# MCU.net
KiCad netlist of a schematic drawn in Altium Designer
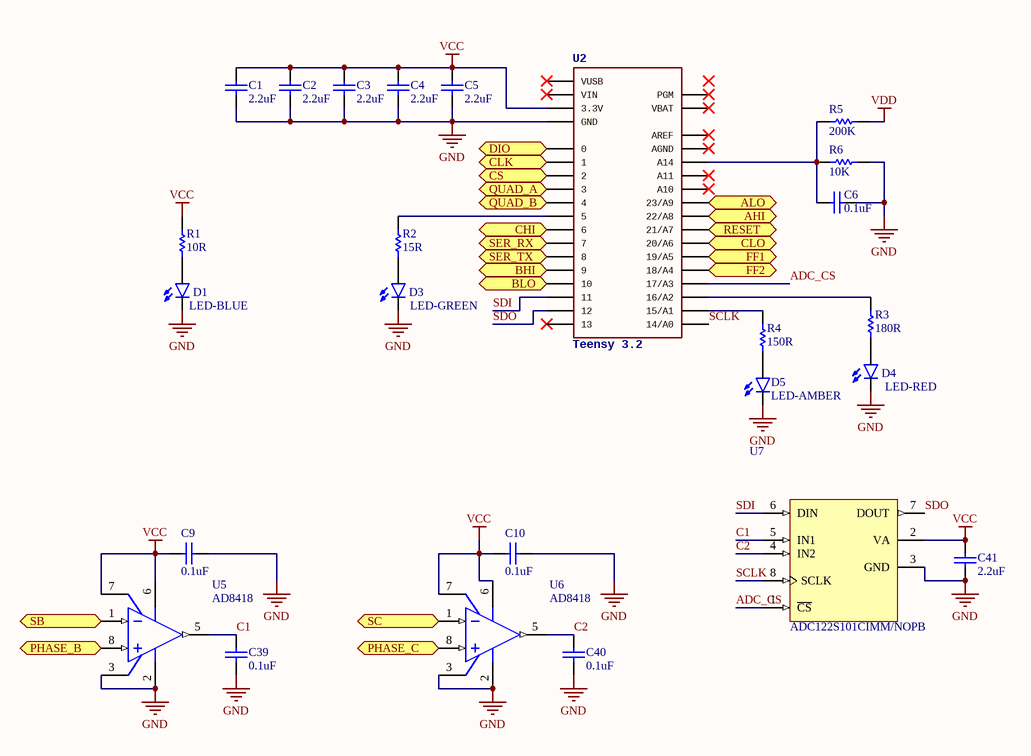
[diagram p0: MCU.SchDoc]

(export (version "E")
  (design (tool "Eeschema 10.0.6"))
  (components
    (comp (ref "C1")
      (value "2.2uF")
      (footprint "CAPC0603(1608)55_N")
      (description "CAP 2.2uF 16V Â±10% 0603 (1608 Metric) Thickness 0.55mm SMD")
      (fields (field (name "TOLERANCE") "Â±10%"))
      (libsource (lib "Altium Content Vault") (part "CMP-1035-02762-1"))
    )
    (comp (ref "C2")
      (value "2.2uF")
      (footprint "CAPC0603(1608)55_N")
      (description "CAP 2.2uF 16V Â±10% 0603 (1608 Metric) Thickness 0.55mm SMD")
      (fields (field (name "TOLERANCE") "Â±10%"))
      (libsource (lib "Altium Content Vault") (part "CMP-1035-02762-1"))
    )
    (comp (ref "C3")
      (value "2.2uF")
      (footprint "CAPC0603(1608)55_N")
      (description "CAP 2.2uF 16V Â±10% 0603 (1608 Metric) Thickness 0.55mm SMD")
      (fields (field (name "TOLERANCE") "Â±10%"))
      (libsource (lib "Altium Content Vault") (part "CMP-1035-02762-1"))
    )
    (comp (ref "C4")
      (value "2.2uF")
      (footprint "CAPC0603(1608)55_N")
      (description "CAP 2.2uF 16V Â±10% 0603 (1608 Metric) Thickness 0.55mm SMD")
      (fields (field (name "TOLERANCE") "Â±10%"))
      (libsource (lib "Altium Content Vault") (part "CMP-1035-02762-1"))
    )
    (comp (ref "C5")
      (value "2.2uF")
      (footprint "CAPC0603(1608)55_N")
      (description "CAP 2.2uF 16V Â±10% 0603 (1608 Metric) Thickness 0.55mm SMD")
      (fields (field (name "TOLERANCE") "Â±10%"))
      (libsource (lib "Altium Content Vault") (part "CMP-1035-02762-1"))
    )
    (comp (ref "C6")
      (value "0.1uF")
      (footprint "CAPC0603(1608)100_L")
      (description "CAP 100nF 50V Â±5% 0603 (1608 Metric) Thickness 1mm SMD")
      (fields (field (name "TOLERANCE") "Â±5%"))
      (libsource (lib "Altium Content Vault") (part "CMP-1035-02591-1"))
    )
    (comp (ref "C9")
      (value "0.1uF")
      (footprint "CAPC0603(1608)100_L")
      (description "CAP 100nF 6.3V Â±20% 0603 (1608 Metric) Thickness 1mm SMD")
      (fields (field (name "TOLERANCE") "Â±20%"))
      (libsource (lib "Altium Content Vault") (part "CMP-1035-02577-1"))
    )
    (comp (ref "C10")
      (value "0.1uF")
      (footprint "CAPC0603(1608)100_L")
      (description "CAP 100nF 6.3V Â±20% 0603 (1608 Metric) Thickness 1mm SMD")
      (fields (field (name "TOLERANCE") "Â±20%"))
      (libsource (lib "Altium Content Vault") (part "CMP-1035-02577-1"))
    )
    (comp (ref "C39")
      (value "0.1uF")
      (footprint "CAPC0603(1608)100_N")
      (description "CAP 100nF 6.3V ±5% 0603 (1608 Metric) Thickness 1mm SMD")
      (fields (field (name "TOLERANCE") "Â±5%"))
      (libsource (lib "Altium Content Vault") (part "CAP"))
    )
    (comp (ref "C40")
      (value "0.1uF")
      (footprint "CAPC0603(1608)100_N")
      (description "CAP 100nF 6.3V ±5% 0603 (1608 Metric) Thickness 1mm SMD")
      (fields (field (name "TOLERANCE") "Â±5%"))
      (libsource (lib "Altium Content Vault") (part "CAP"))
    )
    (comp (ref "C41")
      (value "2.2uF")
      (footprint "CAPC0603(1608)100_M")
      (description "CAP 2.2uF 6.3V ±10% 0603 (1608 Metric) Thickness 1mm SMD")
      (fields (field (name "TOLERANCE") "Â±10%"))
      (libsource (lib "Altium Content Vault") (part "CAP"))
    )
    (comp (ref "D1")
      (value "LED-BLUE")
      (footprint "LED-1206")
      (libsource (lib "Components") (part "LED-BLUE1206"))
    )
    (comp (ref "D3")
      (value "LED-GREEN")
      (footprint "LED-1206")
      (libsource (lib "Components") (part "LED-GREEN1206"))
    )
    (comp (ref "D4")
      (value "LED-RED")
      (footprint "LED-1206")
      (libsource (lib "Components") (part "LED-RED1206"))
    )
    (comp (ref "D5")
      (value "LED-AMBER")
      (footprint "LED-1206")
      (libsource (lib "Components") (part "LED-AMBER1206"))
    )
    (comp (ref "R1")
      (value "10R")
      (footprint "RESC0603(1608)_N")
      (description "10R 0.1W 5% 0603 (1608 Metric)  SMD")
      (fields (field (name "TOLERANCE") "5 %") (field (name "POWER") "0.1 W"))
      (libsource (lib "Altium Content Vault") (part "CMP-1012-00026-1"))
    )
    (comp (ref "R2")
      (value "15R")
      (footprint "RESC0603(1608)_N")
      (description "15R 0.1W 5% 0603 (1608 Metric)  SMD")
      (fields (field (name "TOLERANCE") "5 %") (field (name "POWER") "0.1 W"))
      (libsource (lib "Altium Content Vault") (part "CMP-1012-00030-1"))
    )
    (comp (ref "R3")
      (value "180R")
      (footprint "RESC0603(1608)_N")
      (description "180R 0.1W 5% 0603 (1608 Metric)  SMD")
      (fields (field (name "POWER") "0.1 W") (field (name "TOLERANCE") "5 %"))
      (libsource (lib "Altium Content Vault") (part "CMP-1012-00056-1"))
    )
    (comp (ref "R4")
      (value "150R")
      (footprint "RESC0603(1608)_N")
      (description "150R 0.1W 5% 0603 (1608 Metric)  SMD")
      (fields (field (name "POWER") "0.1 W") (field (name "TOLERANCE") "5 %"))
      (libsource (lib "Altium Content Vault") (part "CMP-1012-00054-1"))
    )
    (comp (ref "R5")
      (value "200K")
      (footprint "RESC0603(1608)_N")
      (description "200K 0.1W 5% 0603 (1608 Metric)  SMD")
      (fields (field (name "POWER") "0.1 W") (field (name "TOLERANCE") "5 %"))
      (libsource (lib "Altium Content Vault") (part "CMP-1012-00129-1"))
    )
    (comp (ref "R6")
      (value "10K")
      (footprint "RESC0603(1608)_N")
      (description "10K 0.1W 5% 0603 (1608 Metric)  SMD")
      (fields (field (name "TOLERANCE") "5 %") (field (name "POWER") "0.1 W"))
      (libsource (lib "Altium Content Vault") (part "RES"))
    )
    (comp (ref "U2")
      (value "Teensy 3.2")
      (footprint "TEENSY_3.0+4")
      (libsource (lib "Teensy3") (part "TEENSY_3.0+4"))
    )
    (comp (ref "U5") (value "AD8418") (footprint "MSOP-8") (libsource (lib "Components") (part "AD8418")))
    (comp (ref "U6") (value "AD8418") (footprint "MSOP-8") (libsource (lib "Components") (part "AD8418")))
    (comp (ref "U7")
      (value "ADC122S101CIMM/NOPB")
      (footprint "MUA08A_N")
      (description "2 Channel, 500 kSPS to 1 MSPS 12-Bit A/D Converter, 8-pin Mini SOIC, Pb-Free")
      (fields (field (name "MANUFACTURER") "National Semiconductor"))
      (libsource (lib "Altium Content Vault") (part "CON-ADC-ADC102S101CIMM"))
    )
  )
  (nets
    (net (code "1") (name "/ADC_CS") (class "Default")
      (node (ref "U2") (pin "17/A3") (pinfunction "17/A3_17/A3") (pintype "passive"))
      (node (ref "U7") (pin "1") (pinfunction "~{CS}_1") (pintype "input"))
    )
    (net (code "2") (name "/AHI") (class "Default")
      (node (ref "U2") (pin "22/A8") (pinfunction "22/A8_22/A8") (pintype "passive"))
    )
    (net (code "3") (name "/ALO") (class "Default")
      (node (ref "U2") (pin "23/A9") (pinfunction "23/A9_23/A9") (pintype "passive"))
    )
    (net (code "4") (name "/BHI") (class "Default")
      (node (ref "U2") (pin "9") (pinfunction "9_9") (pintype "passive"))
    )
    (net (code "5") (name "/BLO") (class "Default")
      (node (ref "U2") (pin "10") (pinfunction "10_10") (pintype "passive"))
    )
    (net (code "6") (name "/C1") (class "Default")
      (node (ref "C39") (pin "2") (pinfunction "2_2") (pintype "passive"))
      (node (ref "U5") (pin "5") (pinfunction "OUT_5") (pintype "output"))
      (node (ref "U7") (pin "5") (pinfunction "IN1_5") (pintype "input"))
    )
    (net (code "7") (name "/C2") (class "Default")
      (node (ref "C40") (pin "2") (pinfunction "2_2") (pintype "passive"))
      (node (ref "U6") (pin "5") (pinfunction "OUT_5") (pintype "output"))
      (node (ref "U7") (pin "4") (pinfunction "IN2_4") (pintype "input"))
    )
    (net (code "8") (name "/CHI") (class "Default")
      (node (ref "U2") (pin "6") (pinfunction "6_6") (pintype "passive"))
    )
    (net (code "9") (name "/CLK") (class "Default")
      (node (ref "U2") (pin "1") (pinfunction "1_1") (pintype "passive"))
    )
    (net (code "10") (name "/CLO") (class "Default")
      (node (ref "U2") (pin "20/A6") (pinfunction "20/A6_20/A6") (pintype "passive"))
    )
    (net (code "11") (name "/CS") (class "Default")
      (node (ref "U2") (pin "2") (pinfunction "2_2") (pintype "passive"))
    )
    (net (code "12") (name "/DIO") (class "Default")
      (node (ref "U2") (pin "0") (pinfunction "0_0") (pintype "passive"))
    )
    (net (code "13") (name "/FF1") (class "Default")
      (node (ref "U2") (pin "19/A5") (pinfunction "19/A5_19/A5") (pintype "passive"))
    )
    (net (code "14") (name "/FF2") (class "Default")
      (node (ref "U2") (pin "18/A4") (pinfunction "18/A4_18/A4") (pintype "passive"))
    )
    (net (code "15") (name "/PHASE_B") (class "Default")
      (node (ref "U5") (pin "8") (pinfunction "IN+_8") (pintype "input"))
    )
    (net (code "16") (name "/PHASE_C") (class "Default")
      (node (ref "U6") (pin "8") (pinfunction "IN+_8") (pintype "input"))
    )
    (net (code "17") (name "/QUAD_A") (class "Default")
      (node (ref "U2") (pin "3") (pinfunction "3_3") (pintype "passive"))
    )
    (net (code "18") (name "/QUAD_B") (class "Default")
      (node (ref "U2") (pin "4") (pinfunction "4_4") (pintype "passive"))
    )
    (net (code "19") (name "/RESET") (class "Default")
      (node (ref "U2") (pin "21/A7") (pinfunction "21/A7_21/A7") (pintype "passive"))
    )
    (net (code "20") (name "/SB") (class "Default")
      (node (ref "U5") (pin "1") (pinfunction "IN-_1") (pintype "input"))
    )
    (net (code "21") (name "/SC") (class "Default")
      (node (ref "U6") (pin "1") (pinfunction "IN-_1") (pintype "input"))
    )
    (net (code "22") (name "/SCLK") (class "Default")
      (node (ref "U2") (pin "14/A0") (pinfunction "14/A0_14/A0") (pintype "passive"))
      (node (ref "U7") (pin "8") (pinfunction "SCLK_8") (pintype "input"))
    )
    (net (code "23") (name "/SDI") (class "Default")
      (node (ref "U2") (pin "11") (pinfunction "11_11") (pintype "passive"))
      (node (ref "U7") (pin "6") (pinfunction "DIN_6") (pintype "input"))
    )
    (net (code "24") (name "/SDO") (class "Default")
      (node (ref "U2") (pin "12") (pinfunction "12_12") (pintype "passive"))
      (node (ref "U7") (pin "7") (pinfunction "DOUT_7") (pintype "output"))
    )
    (net (code "25") (name "/SER_RX") (class "Default")
      (node (ref "U2") (pin "7") (pinfunction "7_7") (pintype "passive"))
    )
    (net (code "26") (name "/SER_TX") (class "Default")
      (node (ref "U2") (pin "8") (pinfunction "8_8") (pintype "passive"))
    )
    (net (code "27") (name "GND") (class "Default")
      (node (ref "C1") (pin "1") (pinfunction "1_1") (pintype "passive"))
      (node (ref "C10") (pin "1") (pinfunction "1_1") (pintype "passive"))
      (node (ref "C2") (pin "1") (pinfunction "1_1") (pintype "passive"))
      (node (ref "C3") (pin "1") (pinfunction "1_1") (pintype "passive"))
      (node (ref "C39") (pin "1") (pinfunction "1_1") (pintype "passive"))
      (node (ref "C4") (pin "1") (pinfunction "1_1") (pintype "passive"))
      (node (ref "C40") (pin "1") (pinfunction "1_1") (pintype "passive"))
      (node (ref "C41") (pin "1") (pinfunction "1_1") (pintype "passive"))
      (node (ref "C5") (pin "1") (pinfunction "1_1") (pintype "passive"))
      (node (ref "C6") (pin "2") (pinfunction "2_2") (pintype "passive"))
      (node (ref "C9") (pin "1") (pinfunction "1_1") (pintype "passive"))
      (node (ref "D1") (pin "C") (pinfunction "C_C") (pintype "passive"))
      (node (ref "D3") (pin "C") (pinfunction "C_C") (pintype "passive"))
      (node (ref "D4") (pin "C") (pinfunction "C_C") (pintype "passive"))
      (node (ref "D5") (pin "C") (pinfunction "C_C") (pintype "passive"))
      (node (ref "R6") (pin "2") (pinfunction "2_2") (pintype "passive"))
      (node (ref "U2") (pin "GND_GND1") (pinfunction "GND_GND_GND1") (pintype "power_in"))
      (node (ref "U5") (pin "2") (pinfunction "GND_2") (pintype "power_in"))
      (node (ref "U5") (pin "3") (pinfunction "VREF2_3") (pintype "passive"))
      (node (ref "U6") (pin "2") (pinfunction "GND_2") (pintype "power_in"))
      (node (ref "U6") (pin "3") (pinfunction "VREF2_3") (pintype "passive"))
      (node (ref "U7") (pin "3") (pinfunction "GND_3") (pintype "power_in"))
    )
    (net (code "28") (name "Net-(C6-Pad1)") (class "Default")
      (node (ref "C6") (pin "1") (pinfunction "1_1") (pintype "passive"))
      (node (ref "R5") (pin "1") (pinfunction "1_1") (pintype "passive"))
      (node (ref "R6") (pin "1") (pinfunction "1_1") (pintype "passive"))
      (node (ref "U2") (pin "A14") (pinfunction "A14_A14") (pintype "passive"))
    )
    (net (code "29") (name "Net-(D1-PadA)") (class "Default")
      (node (ref "D1") (pin "A") (pinfunction "A_A") (pintype "passive"))
      (node (ref "R1") (pin "1") (pinfunction "1_1") (pintype "passive"))
    )
    (net (code "30") (name "Net-(D3-PadA)") (class "Default")
      (node (ref "D3") (pin "A") (pinfunction "A_A") (pintype "passive"))
      (node (ref "R2") (pin "1") (pinfunction "1_1") (pintype "passive"))
    )
    (net (code "31") (name "Net-(D4-PadA)") (class "Default")
      (node (ref "D4") (pin "A") (pinfunction "A_A") (pintype "passive"))
      (node (ref "R3") (pin "1") (pinfunction "1_1") (pintype "passive"))
    )
    (net (code "32") (name "Net-(D5-PadA)") (class "Default")
      (node (ref "D5") (pin "A") (pinfunction "A_A") (pintype "passive"))
      (node (ref "R4") (pin "1") (pinfunction "1_1") (pintype "passive"))
    )
    (net (code "33") (name "Net-(R2-Pad2)") (class "Default")
      (node (ref "R2") (pin "2") (pinfunction "2_2") (pintype "passive"))
      (node (ref "U2") (pin "5") (pinfunction "5_5") (pintype "passive"))
    )
    (net (code "34") (name "Net-(R3-Pad2)") (class "Default")
      (node (ref "R3") (pin "2") (pinfunction "2_2") (pintype "passive"))
      (node (ref "U2") (pin "16/A2") (pinfunction "16/A2_16/A2") (pintype "passive"))
    )
    (net (code "35") (name "Net-(R4-Pad2)") (class "Default")
      (node (ref "R4") (pin "2") (pinfunction "2_2") (pintype "passive"))
      (node (ref "U2") (pin "15/A1") (pinfunction "15/A1_15/A1") (pintype "passive"))
    )
    (net (code "36") (name "VCC") (class "Default")
      (node (ref "C1") (pin "2") (pinfunction "2_2") (pintype "passive"))
      (node (ref "C10") (pin "2") (pinfunction "2_2") (pintype "passive"))
      (node (ref "C2") (pin "2") (pinfunction "2_2") (pintype "passive"))
      (node (ref "C3") (pin "2") (pinfunction "2_2") (pintype "passive"))
      (node (ref "C4") (pin "2") (pinfunction "2_2") (pintype "passive"))
      (node (ref "C41") (pin "2") (pinfunction "2_2") (pintype "passive"))
      (node (ref "C5") (pin "2") (pinfunction "2_2") (pintype "passive"))
      (node (ref "C9") (pin "2") (pinfunction "2_2") (pintype "passive"))
      (node (ref "R1") (pin "2") (pinfunction "2_2") (pintype "passive"))
      (node (ref "U2") (pin "3.3V_3.3V1") (pinfunction "3.3V_3.3V_3.3V1") (pintype "power_in"))
      (node (ref "U5") (pin "6") (pinfunction "VS_6") (pintype "power_in"))
      (node (ref "U5") (pin "7") (pinfunction "VREF1_7") (pintype "passive"))
      (node (ref "U6") (pin "6") (pinfunction "VS_6") (pintype "power_in"))
      (node (ref "U6") (pin "7") (pinfunction "VREF1_7") (pintype "passive"))
      (node (ref "U7") (pin "2") (pinfunction "VA_2") (pintype "power_in"))
    )
    (net (code "37") (name "VDD") (class "Default")
      (node (ref "R5") (pin "2") (pinfunction "2_2") (pintype "passive"))
    )
    (net (code "38") (name "unconnected-(U2-Pad13)") (class "Default")
      (node (ref "U2") (pin "13") (pinfunction "13_13") (pintype "passive+no_connect"))
    )
    (net (code "39") (name "unconnected-(U2-PadA10)") (class "Default")
      (node (ref "U2") (pin "A10") (pinfunction "A10_A10") (pintype "passive+no_connect"))
    )
    (net (code "40") (name "unconnected-(U2-PadA11)") (class "Default")
      (node (ref "U2") (pin "A11") (pinfunction "A11_A11") (pintype "passive+no_connect"))
    )
    (net (code "41") (name "unconnected-(U2-PadAGND)") (class "Default")
      (node (ref "U2") (pin "AGND") (pinfunction "AGND_AGND") (pintype "power_in+no_connect"))
    )
    (net (code "42") (name "unconnected-(U2-PadAREF)") (class "Default")
      (node (ref "U2") (pin "AREF") (pinfunction "AREF_AREF") (pintype "power_in+no_connect"))
    )
    (net (code "43") (name "unconnected-(U2-PadPGM)") (class "Default")
      (node (ref "U2") (pin "PGM") (pinfunction "PGM_PGM") (pintype "passive+no_connect"))
    )
    (net (code "44") (name "unconnected-(U2-PadVBAT)") (class "Default")
      (node (ref "U2") (pin "VBAT") (pinfunction "VBAT_VBAT") (pintype "power_in+no_connect"))
    )
    (net (code "45") (name "unconnected-(U2-PadVIN)") (class "Default")
      (node (ref "U2") (pin "VIN") (pinfunction "VIN_VIN") (pintype "power_in+no_connect"))
    )
    (net (code "46") (name "unconnected-(U2-PadVUSB)") (class "Default")
      (node (ref "U2") (pin "VUSB") (pinfunction "VUSB_VUSB") (pintype "power_in+no_connect"))
    )
  )
)
